# zxld383-boost-driver-12mm-mk-3-led.net
KiCad netlist of a schematic drawn in EAGLE
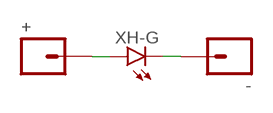
[diagram p0: schematic, sheet 1]

(export (version "E")
  (design (tool "Eeschema 10.0.6"))
  (components
    (comp (ref "+")
      (value "M01PTH-1.2MM")
      (footprint "eagle-import:1X01-1.2MM")
      (libsource (lib "eagle-import") (part "M01PTH-1.2MM"))
    )
    (comp (ref "-")
      (value "M01PTH-1.2MM-NS")
      (footprint "eagle-import:1X01-1.2MM-NS")
      (libsource (lib "eagle-import") (part "M01PTH-1.2MM-NS"))
    )
    (comp (ref "XH-G")
      (value "LEDXH-G")
      (footprint "eagle-import:CREE-XLAMP-XH-G")
      (libsource (lib "eagle-import") (part "LEDXH-G"))
    )
  )
  (nets
    (net (code "1") (name "Net-(+-1)") (class "Default")
      (node (ref "+") (pin "P$1") (pinfunction "1_P$1") (pintype "passive"))
      (node (ref "XH-G") (pin "A") (pinfunction "A_A") (pintype "passive"))
    )
    (net (code "2") (name "Net-(--1)") (class "Default")
      (node (ref "-") (pin "P$1") (pinfunction "1_P$1") (pintype "passive"))
      (node (ref "XH-G") (pin "K") (pinfunction "C_K") (pintype "passive"))
      (node (ref "XH-G") (pin "K@1") (pinfunction "C_K@1") (pintype "passive"))
      (node (ref "XH-G") (pin "K@2") (pinfunction "C_K@2") (pintype "passive"))
      (node (ref "XH-G") (pin "K@3") (pinfunction "C_K@3") (pintype "passive"))
      (node (ref "XH-G") (pin "K@4") (pinfunction "C_K@4") (pintype "passive"))
      (node (ref "XH-G") (pin "K@5") (pinfunction "C_K@5") (pintype "passive"))
      (node (ref "XH-G") (pin "K@6") (pinfunction "C_K@6") (pintype "passive"))
      (node (ref "XH-G") (pin "K@7") (pinfunction "C_K@7") (pintype "passive"))
      (node (ref "XH-G") (pin "K@8") (pinfunction "C_K@8") (pintype "passive"))
    )
  )
)
